# Num_PreDesign.net
KiCad netlist of a schematic drawn in Altium Designer
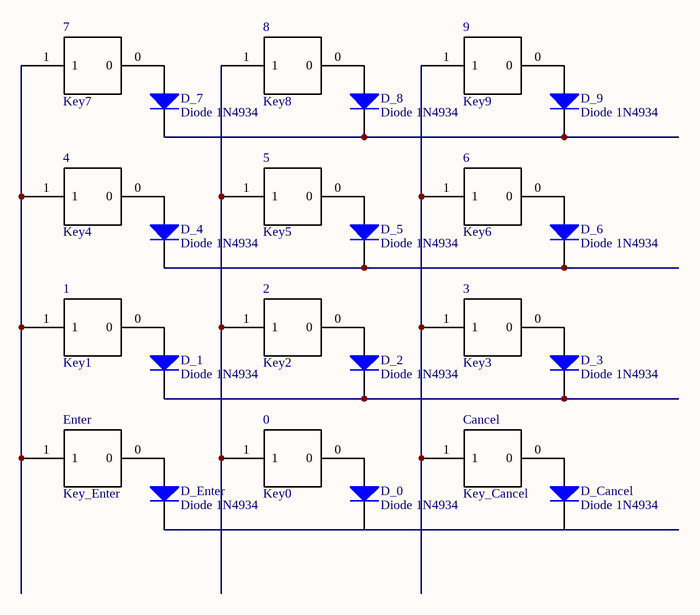
[diagram p0: Num_PreDesign.SchDoc]

(export (version "E")
  (design (tool "Eeschema 10.0.6"))
  (components
    (comp (ref "0")
      (value "Key0")
      (footprint "Cherry Standard MX Switch")
      (libsource (lib "KeyBoard") (part "Cherry MX"))
    )
    (comp (ref "1")
      (value "Key1")
      (footprint "Cherry Standard MX Switch")
      (libsource (lib "KeyBoard") (part "Cherry MX"))
    )
    (comp (ref "2")
      (value "Key2")
      (footprint "Cherry Standard MX Switch")
      (libsource (lib "KeyBoard") (part "Cherry MX"))
    )
    (comp (ref "3")
      (value "Key3")
      (footprint "Cherry Standard MX Switch")
      (libsource (lib "KeyBoard") (part "Cherry MX"))
    )
    (comp (ref "4")
      (value "Key4")
      (footprint "Cherry Standard MX Switch")
      (libsource (lib "KeyBoard") (part "Cherry MX"))
    )
    (comp (ref "5")
      (value "Key5")
      (footprint "Cherry Standard MX Switch")
      (libsource (lib "KeyBoard") (part "Cherry MX"))
    )
    (comp (ref "6")
      (value "Key6")
      (footprint "Cherry Standard MX Switch")
      (libsource (lib "KeyBoard") (part "Cherry MX"))
    )
    (comp (ref "7")
      (value "Key7")
      (footprint "Cherry Standard MX Switch")
      (libsource (lib "KeyBoard") (part "Cherry MX"))
    )
    (comp (ref "8")
      (value "Key8")
      (footprint "Cherry Standard MX Switch")
      (libsource (lib "KeyBoard") (part "Cherry MX"))
    )
    (comp (ref "9")
      (value "Key9")
      (footprint "Cherry Standard MX Switch")
      (libsource (lib "KeyBoard") (part "Cherry MX"))
    )
    (comp (ref "Cancel")
      (value "Key_Cancel")
      (footprint "Cherry Standard MX Switch")
      (libsource (lib "KeyBoard") (part "Cherry MX"))
    )
    (comp (ref "D_0")
      (value "Diode 1N4934")
      (footprint "DO-41")
      (description "1 Amp Fast Recovery Rectifier")
      (fields (field (name "PUBLISHER") "Altium Limited"))
      (libsource (lib "Miscellaneous Devices") (part "Diode 1N4934"))
    )
    (comp (ref "D_1")
      (value "Diode 1N4934")
      (footprint "DO-41")
      (description "1 Amp Fast Recovery Rectifier")
      (fields (field (name "PUBLISHER") "Altium Limited"))
      (libsource (lib "Miscellaneous Devices") (part "Diode 1N4934"))
    )
    (comp (ref "D_2")
      (value "Diode 1N4934")
      (footprint "DO-41")
      (description "1 Amp Fast Recovery Rectifier")
      (fields (field (name "PUBLISHER") "Altium Limited"))
      (libsource (lib "Miscellaneous Devices") (part "Diode 1N4934"))
    )
    (comp (ref "D_3")
      (value "Diode 1N4934")
      (footprint "DO-41")
      (description "1 Amp Fast Recovery Rectifier")
      (fields (field (name "PUBLISHER") "Altium Limited"))
      (libsource (lib "Miscellaneous Devices") (part "Diode 1N4934"))
    )
    (comp (ref "D_4")
      (value "Diode 1N4934")
      (footprint "DO-41")
      (description "1 Amp Fast Recovery Rectifier")
      (fields (field (name "PUBLISHER") "Altium Limited"))
      (libsource (lib "Miscellaneous Devices") (part "Diode 1N4934"))
    )
    (comp (ref "D_5")
      (value "Diode 1N4934")
      (footprint "DO-41")
      (description "1 Amp Fast Recovery Rectifier")
      (fields (field (name "PUBLISHER") "Altium Limited"))
      (libsource (lib "Miscellaneous Devices") (part "Diode 1N4934"))
    )
    (comp (ref "D_6")
      (value "Diode 1N4934")
      (footprint "DO-41")
      (description "1 Amp Fast Recovery Rectifier")
      (fields (field (name "PUBLISHER") "Altium Limited"))
      (libsource (lib "Miscellaneous Devices") (part "Diode 1N4934"))
    )
    (comp (ref "D_7")
      (value "Diode 1N4934")
      (footprint "DO-41")
      (description "1 Amp Fast Recovery Rectifier")
      (fields (field (name "PUBLISHER") "Altium Limited"))
      (libsource (lib "Miscellaneous Devices") (part "Diode 1N4934"))
    )
    (comp (ref "D_8")
      (value "Diode 1N4934")
      (footprint "DO-41")
      (description "1 Amp Fast Recovery Rectifier")
      (fields (field (name "PUBLISHER") "Altium Limited"))
      (libsource (lib "Miscellaneous Devices") (part "Diode 1N4934"))
    )
    (comp (ref "D_9")
      (value "Diode 1N4934")
      (footprint "DO-41")
      (description "1 Amp Fast Recovery Rectifier")
      (fields (field (name "PUBLISHER") "Altium Limited"))
      (libsource (lib "Miscellaneous Devices") (part "Diode 1N4934"))
    )
    (comp (ref "D_Cancel")
      (value "Diode 1N4934")
      (footprint "DO-41")
      (description "1 Amp Fast Recovery Rectifier")
      (fields (field (name "PUBLISHER") "Altium Limited"))
      (libsource (lib "Miscellaneous Devices") (part "Diode 1N4934"))
    )
    (comp (ref "D_Enter")
      (value "Diode 1N4934")
      (footprint "DO-41")
      (description "1 Amp Fast Recovery Rectifier")
      (fields (field (name "PUBLISHER") "Altium Limited"))
      (libsource (lib "Miscellaneous Devices") (part "Diode 1N4934"))
    )
    (comp (ref "Enter")
      (value "Key_Enter")
      (footprint "Cherry Standard MX Switch")
      (libsource (lib "KeyBoard") (part "Cherry MX"))
    )
  )
  (nets
    (net (code "1") (name "Net-(0-Pad1)") (class "Default")
      (node (ref "0") (pin "1") (pinfunction "1_1") (pintype "passive"))
      (node (ref "2") (pin "1") (pinfunction "1_1") (pintype "passive"))
      (node (ref "5") (pin "1") (pinfunction "1_1") (pintype "passive"))
      (node (ref "8") (pin "1") (pinfunction "1_1") (pintype "passive"))
    )
    (net (code "2") (name "Net-(1-Pad1)") (class "Default")
      (node (ref "1") (pin "1") (pinfunction "1_1") (pintype "passive"))
      (node (ref "4") (pin "1") (pinfunction "1_1") (pintype "passive"))
      (node (ref "7") (pin "1") (pinfunction "1_1") (pintype "passive"))
      (node (ref "Enter") (pin "1") (pinfunction "1_1") (pintype "passive"))
    )
    (net (code "3") (name "Net-(3-Pad1)") (class "Default")
      (node (ref "3") (pin "1") (pinfunction "1_1") (pintype "passive"))
      (node (ref "6") (pin "1") (pinfunction "1_1") (pintype "passive"))
      (node (ref "9") (pin "1") (pinfunction "1_1") (pintype "passive"))
      (node (ref "Cancel") (pin "1") (pinfunction "1_1") (pintype "passive"))
    )
    (net (code "4") (name "Net-(D_0-A)") (class "Default")
      (node (ref "0") (pin "0") (pinfunction "0_0") (pintype "passive"))
      (node (ref "D_0") (pin "1") (pinfunction "A_1") (pintype "passive"))
    )
    (net (code "5") (name "Net-(D_0-K)") (class "Default")
      (node (ref "D_0") (pin "2") (pinfunction "K_2") (pintype "passive"))
      (node (ref "D_Cancel") (pin "2") (pinfunction "K_2") (pintype "passive"))
      (node (ref "D_Enter") (pin "2") (pinfunction "K_2") (pintype "passive"))
    )
    (net (code "6") (name "Net-(D_1-A)") (class "Default")
      (node (ref "1") (pin "0") (pinfunction "0_0") (pintype "passive"))
      (node (ref "D_1") (pin "1") (pinfunction "A_1") (pintype "passive"))
    )
    (net (code "7") (name "Net-(D_1-K)") (class "Default")
      (node (ref "D_1") (pin "2") (pinfunction "K_2") (pintype "passive"))
      (node (ref "D_2") (pin "2") (pinfunction "K_2") (pintype "passive"))
      (node (ref "D_3") (pin "2") (pinfunction "K_2") (pintype "passive"))
    )
    (net (code "8") (name "Net-(D_2-A)") (class "Default")
      (node (ref "2") (pin "0") (pinfunction "0_0") (pintype "passive"))
      (node (ref "D_2") (pin "1") (pinfunction "A_1") (pintype "passive"))
    )
    (net (code "9") (name "Net-(D_3-A)") (class "Default")
      (node (ref "3") (pin "0") (pinfunction "0_0") (pintype "passive"))
      (node (ref "D_3") (pin "1") (pinfunction "A_1") (pintype "passive"))
    )
    (net (code "10") (name "Net-(D_4-A)") (class "Default")
      (node (ref "4") (pin "0") (pinfunction "0_0") (pintype "passive"))
      (node (ref "D_4") (pin "1") (pinfunction "A_1") (pintype "passive"))
    )
    (net (code "11") (name "Net-(D_4-K)") (class "Default")
      (node (ref "D_4") (pin "2") (pinfunction "K_2") (pintype "passive"))
      (node (ref "D_5") (pin "2") (pinfunction "K_2") (pintype "passive"))
      (node (ref "D_6") (pin "2") (pinfunction "K_2") (pintype "passive"))
    )
    (net (code "12") (name "Net-(D_5-A)") (class "Default")
      (node (ref "5") (pin "0") (pinfunction "0_0") (pintype "passive"))
      (node (ref "D_5") (pin "1") (pinfunction "A_1") (pintype "passive"))
    )
    (net (code "13") (name "Net-(D_6-A)") (class "Default")
      (node (ref "6") (pin "0") (pinfunction "0_0") (pintype "passive"))
      (node (ref "D_6") (pin "1") (pinfunction "A_1") (pintype "passive"))
    )
    (net (code "14") (name "Net-(D_7-A)") (class "Default")
      (node (ref "7") (pin "0") (pinfunction "0_0") (pintype "passive"))
      (node (ref "D_7") (pin "1") (pinfunction "A_1") (pintype "passive"))
    )
    (net (code "15") (name "Net-(D_7-K)") (class "Default")
      (node (ref "D_7") (pin "2") (pinfunction "K_2") (pintype "passive"))
      (node (ref "D_8") (pin "2") (pinfunction "K_2") (pintype "passive"))
      (node (ref "D_9") (pin "2") (pinfunction "K_2") (pintype "passive"))
    )
    (net (code "16") (name "Net-(D_8-A)") (class "Default")
      (node (ref "8") (pin "0") (pinfunction "0_0") (pintype "passive"))
      (node (ref "D_8") (pin "1") (pinfunction "A_1") (pintype "passive"))
    )
    (net (code "17") (name "Net-(D_9-A)") (class "Default")
      (node (ref "9") (pin "0") (pinfunction "0_0") (pintype "passive"))
      (node (ref "D_9") (pin "1") (pinfunction "A_1") (pintype "passive"))
    )
    (net (code "18") (name "Net-(D_Cancel-A)") (class "Default")
      (node (ref "Cancel") (pin "0") (pinfunction "0_0") (pintype "passive"))
      (node (ref "D_Cancel") (pin "1") (pinfunction "A_1") (pintype "passive"))
    )
    (net (code "19") (name "Net-(D_Enter-A)") (class "Default")
      (node (ref "D_Enter") (pin "1") (pinfunction "A_1") (pintype "passive"))
      (node (ref "Enter") (pin "0") (pinfunction "0_0") (pintype "passive"))
    )
  )
)
